# HMC6343_Breakout.net
KiCad netlist of a schematic drawn in EAGLE
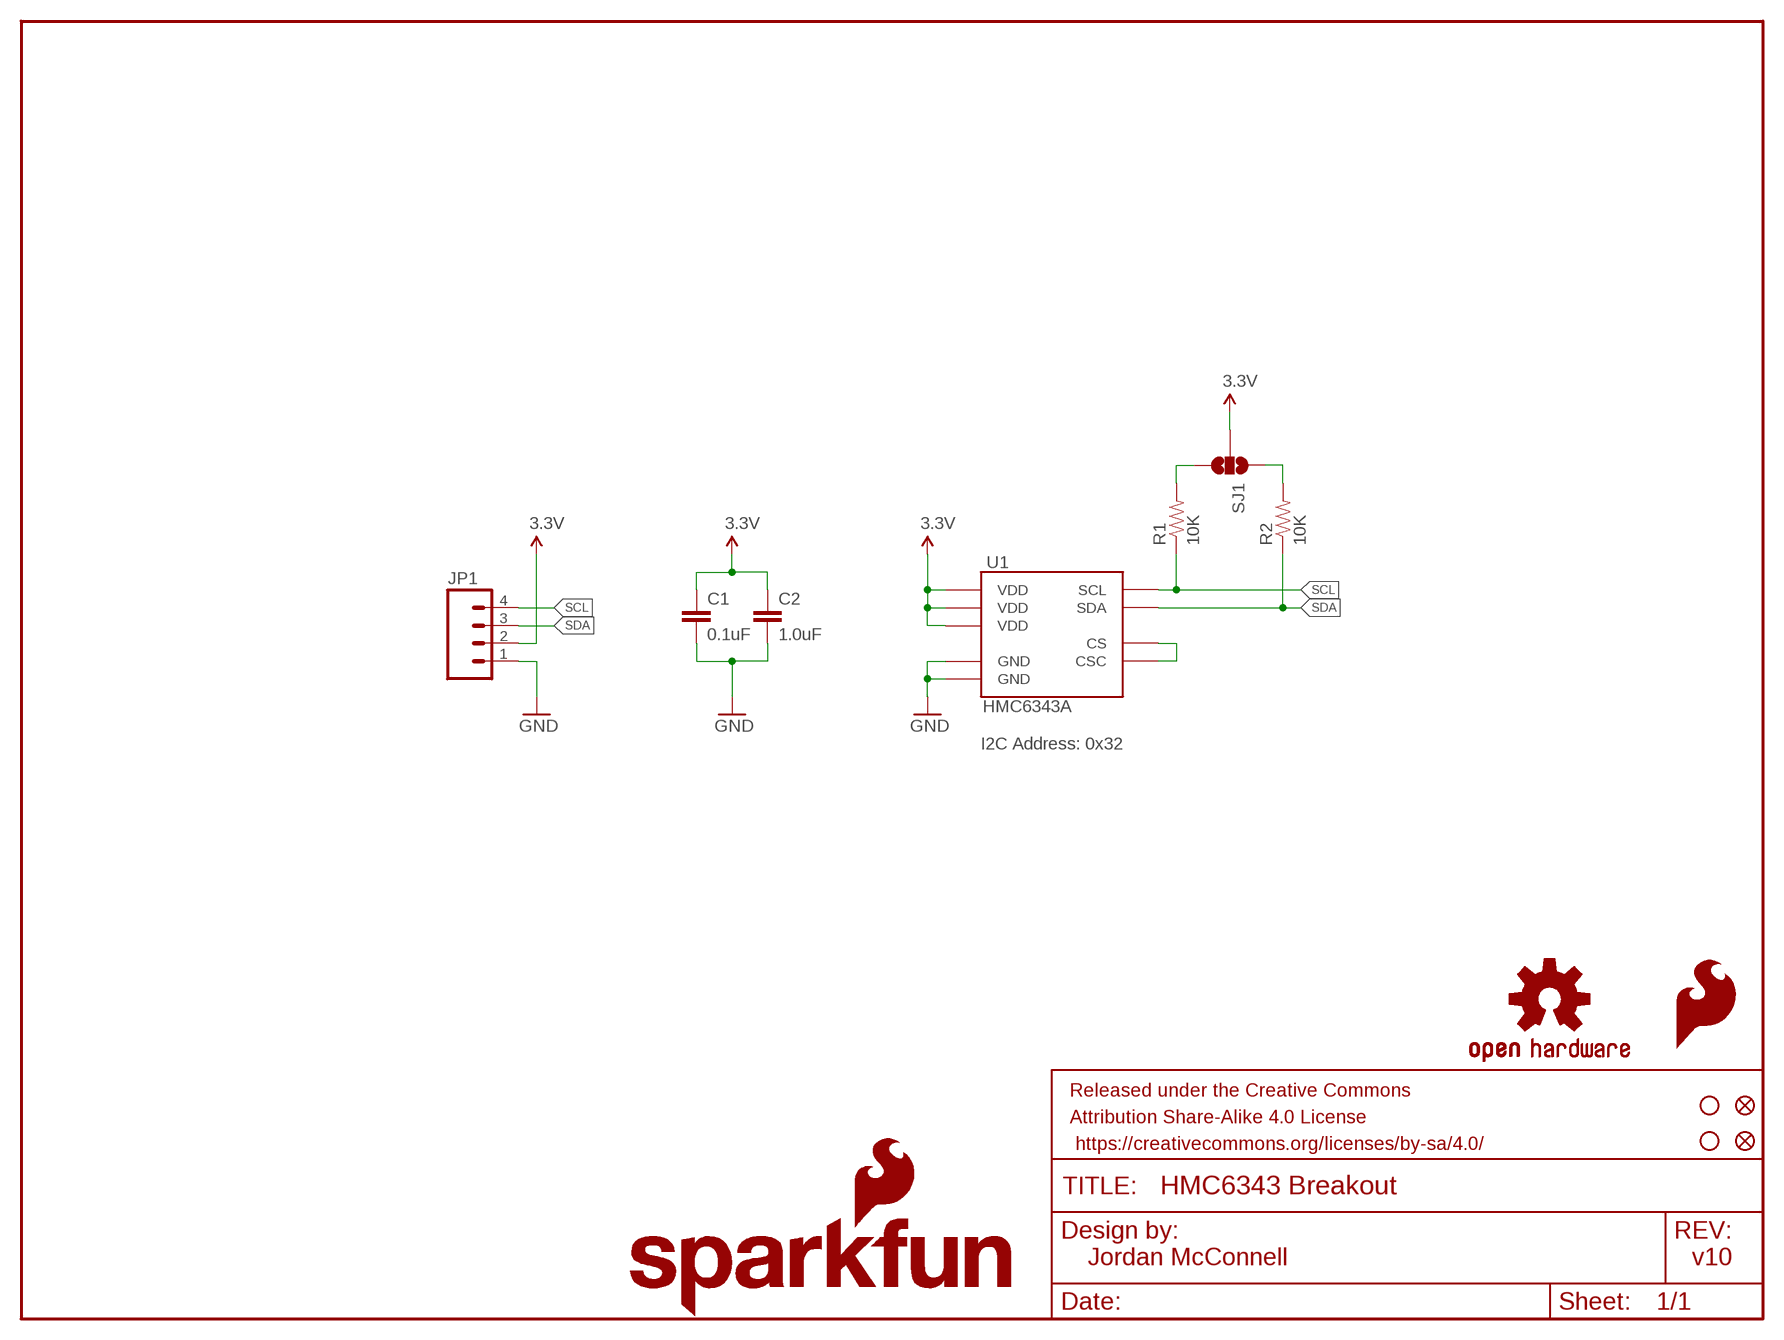
[diagram p0: schematic, sheet 1]

(export (version "E")
  (design (tool "Eeschema 10.0.6"))
  (components
    (comp (ref "C1")
      (value "0.1uF")
      (footprint "eagle-import:0603-CAP")
      (libsource (lib "eagle-import") (part "0.1UF-25V(+80/-20%)(0603)"))
    )
    (comp (ref "C2")
      (value "1.0uF")
      (footprint "eagle-import:0603-CAP")
      (libsource (lib "eagle-import") (part "1.0UF-16V-10%(0603)"))
    )
    (comp (ref "FID1")
      (value "FIDUCIAL1X2")
      (footprint "eagle-import:FIDUCIAL-1X2")
      (libsource (lib "eagle-import") (part "FIDUCIAL1X2"))
    )
    (comp (ref "FID2")
      (value "FIDUCIAL1X2")
      (footprint "eagle-import:FIDUCIAL-1X2")
      (libsource (lib "eagle-import") (part "FIDUCIAL1X2"))
    )
    (comp (ref "FRAME1")
      (value "FRAME-LETTER")
      (footprint "eagle-import:CREATIVE_COMMONS")
      (libsource (lib "eagle-import") (part "FRAME-LETTER"))
    )
    (comp (ref "JP1")
      (value "M04PTH")
      (footprint "eagle-import:1X04")
      (libsource (lib "eagle-import") (part "M04PTH"))
    )
    (comp (ref "LOGO1")
      (value "SFE_LOGO_FLAME.1_INCH")
      (footprint "eagle-import:SFE_LOGO_FLAME_.1")
      (libsource (lib "eagle-import") (part "SFE_LOGO_FLAME.1_INCH"))
    )
    (comp (ref "LOGO2")
      (value "SFE_LOGO_NAME_FLAME.1_INCH")
      (footprint "eagle-import:SFE_LOGO_NAME_FLAME_.1")
      (libsource (lib "eagle-import") (part "SFE_LOGO_NAME_FLAME.1_INCH"))
    )
    (comp (ref "LOGO3")
      (value "OSHW-LOGOS")
      (footprint "eagle-import:OSHW-LOGO-S")
      (libsource (lib "eagle-import") (part "OSHW-LOGOS"))
    )
    (comp (ref "R1")
      (value "10K")
      (footprint "eagle-import:0603-RES")
      (libsource (lib "eagle-import") (part "10KOHM1/10W1%(0603)0603"))
    )
    (comp (ref "R2")
      (value "10K")
      (footprint "eagle-import:0603-RES")
      (libsource (lib "eagle-import") (part "10KOHM1/10W1%(0603)0603"))
    )
    (comp (ref "SJ1")
      (value "SOLDERJUMPER_2WAYPASTE1&2&3")
      (footprint "eagle-import:SJ_3_PASTE1&2&3")
      (libsource (lib "eagle-import") (part "SOLDERJUMPER_2WAYPASTE1&2&3"))
    )
    (comp (ref "STANDOFF1")
      (value "STAND-OFF")
      (footprint "eagle-import:STAND-OFF")
      (libsource (lib "eagle-import") (part "STAND-OFF"))
    )
    (comp (ref "STANDOFF2")
      (value "STAND-OFF")
      (footprint "eagle-import:STAND-OFF")
      (libsource (lib "eagle-import") (part "STAND-OFF"))
    )
    (comp (ref "U1")
      (value "HMC6343A")
      (footprint "eagle-import:LCC36")
      (libsource (lib "eagle-import") (part "HMC6343A"))
    )
  )
  (nets
    (net (code "1") (name "3.3V") (class "Default")
      (node (ref "C1") (pin "1") (pinfunction "1_1") (pintype "passive"))
      (node (ref "C2") (pin "1") (pinfunction "1_1") (pintype "passive"))
      (node (ref "JP1") (pin "2") (pinfunction "2_2") (pintype "passive"))
      (node (ref "SJ1") (pin "2") (pinfunction "2_2") (pintype "passive"))
      (node (ref "U1") (pin "11") (pinfunction "VDD_11") (pintype "bidirectional"))
      (node (ref "U1") (pin "21") (pinfunction "VDD_21") (pintype "bidirectional"))
      (node (ref "U1") (pin "3") (pinfunction "VDD_3") (pintype "bidirectional"))
    )
    (net (code "2") (name "GND") (class "Default")
      (node (ref "C1") (pin "2") (pinfunction "2_2") (pintype "passive"))
      (node (ref "C2") (pin "2") (pinfunction "2_2") (pintype "passive"))
      (node (ref "JP1") (pin "1") (pinfunction "1_1") (pintype "passive"))
      (node (ref "U1") (pin "25") (pinfunction "GND_25") (pintype "bidirectional"))
      (node (ref "U1") (pin "29") (pinfunction "GND_29") (pintype "bidirectional"))
    )
    (net (code "3") (name "Net-(R1-Pad2)") (class "Default")
      (node (ref "R1") (pin "2") (pinfunction "2_2") (pintype "passive"))
      (node (ref "SJ1") (pin "3") (pinfunction "3_3") (pintype "passive"))
    )
    (net (code "4") (name "Net-(R2-Pad2)") (class "Default")
      (node (ref "R2") (pin "2") (pinfunction "2_2") (pintype "passive"))
      (node (ref "SJ1") (pin "1") (pinfunction "1_1") (pintype "passive"))
    )
    (net (code "5") (name "Net-(U1-CS)") (class "Default")
      (node (ref "U1") (pin "22") (pinfunction "CS_22") (pintype "bidirectional"))
      (node (ref "U1") (pin "35") (pinfunction "CSC_35") (pintype "bidirectional"))
    )
    (net (code "6") (name "SCL") (class "Default")
      (node (ref "JP1") (pin "4") (pinfunction "4_4") (pintype "passive"))
      (node (ref "R1") (pin "1") (pinfunction "1_1") (pintype "passive"))
      (node (ref "U1") (pin "32") (pinfunction "SCL_32") (pintype "bidirectional"))
    )
    (net (code "7") (name "SDA") (class "Default")
      (node (ref "JP1") (pin "3") (pinfunction "3_3") (pintype "passive"))
      (node (ref "R2") (pin "1") (pinfunction "1_1") (pintype "passive"))
      (node (ref "U1") (pin "36") (pinfunction "SDA_36") (pintype "bidirectional"))
    )
  )
)
